# sensor.net
KiCad netlist of a schematic drawn in EAGLE
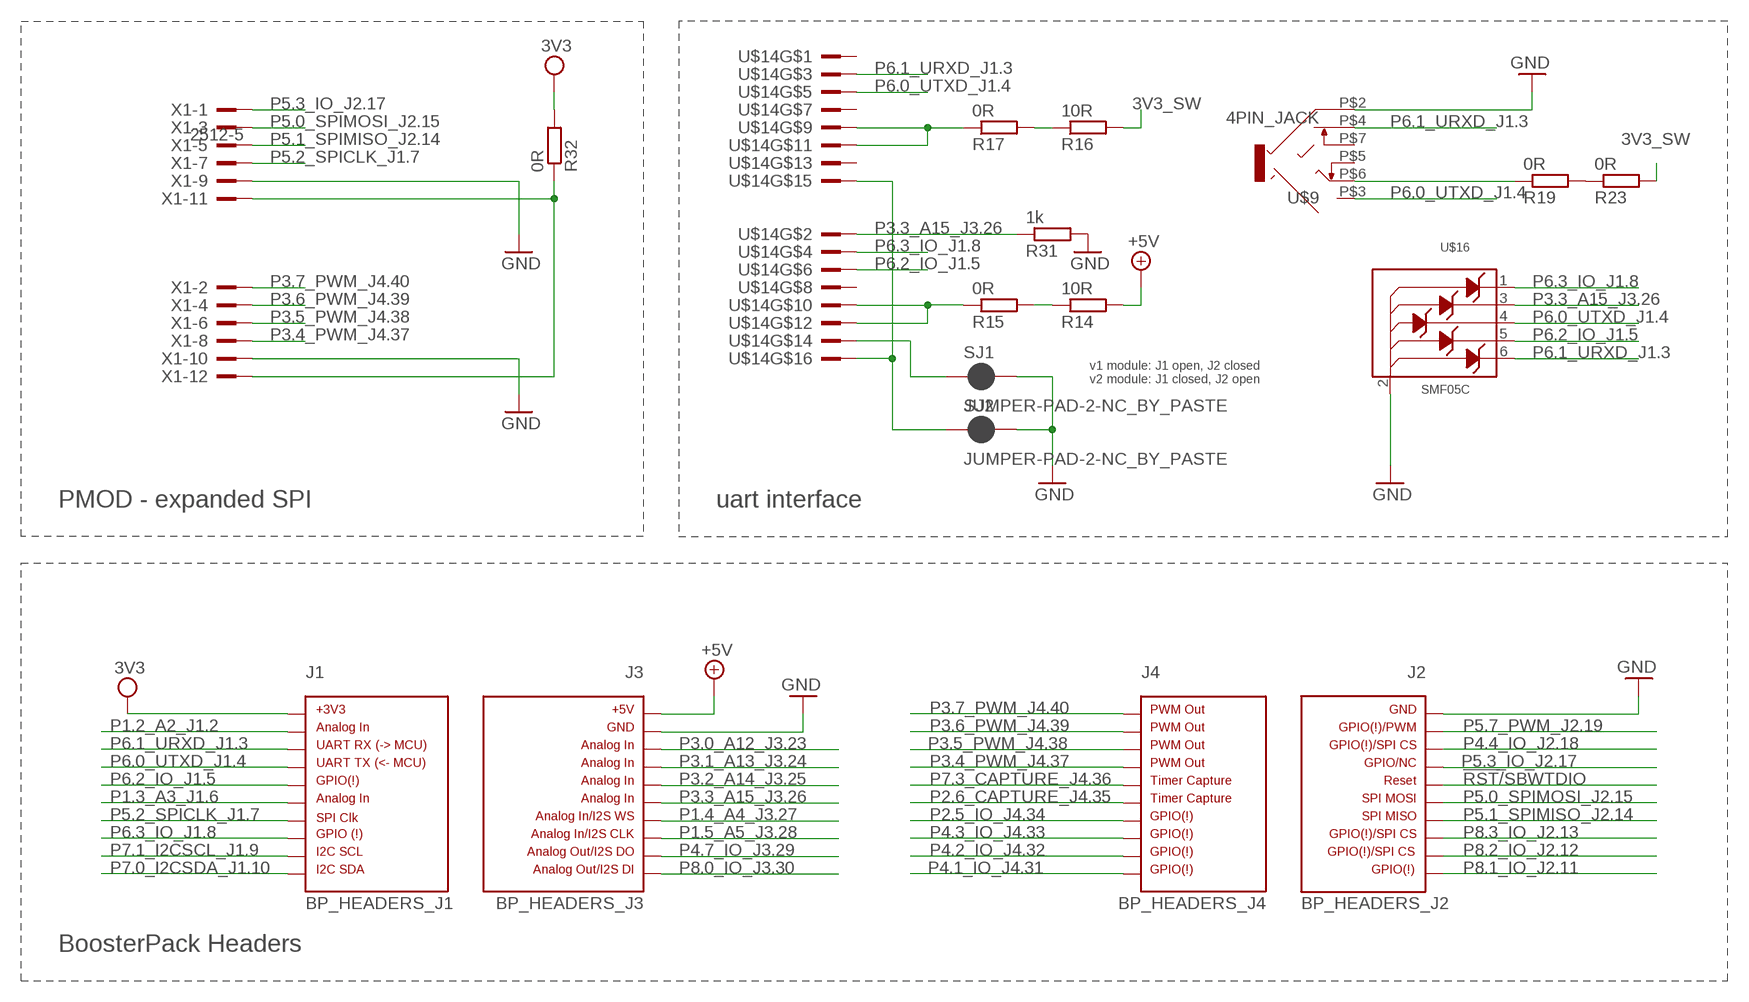
[diagram p0: schematic, sheet 1]
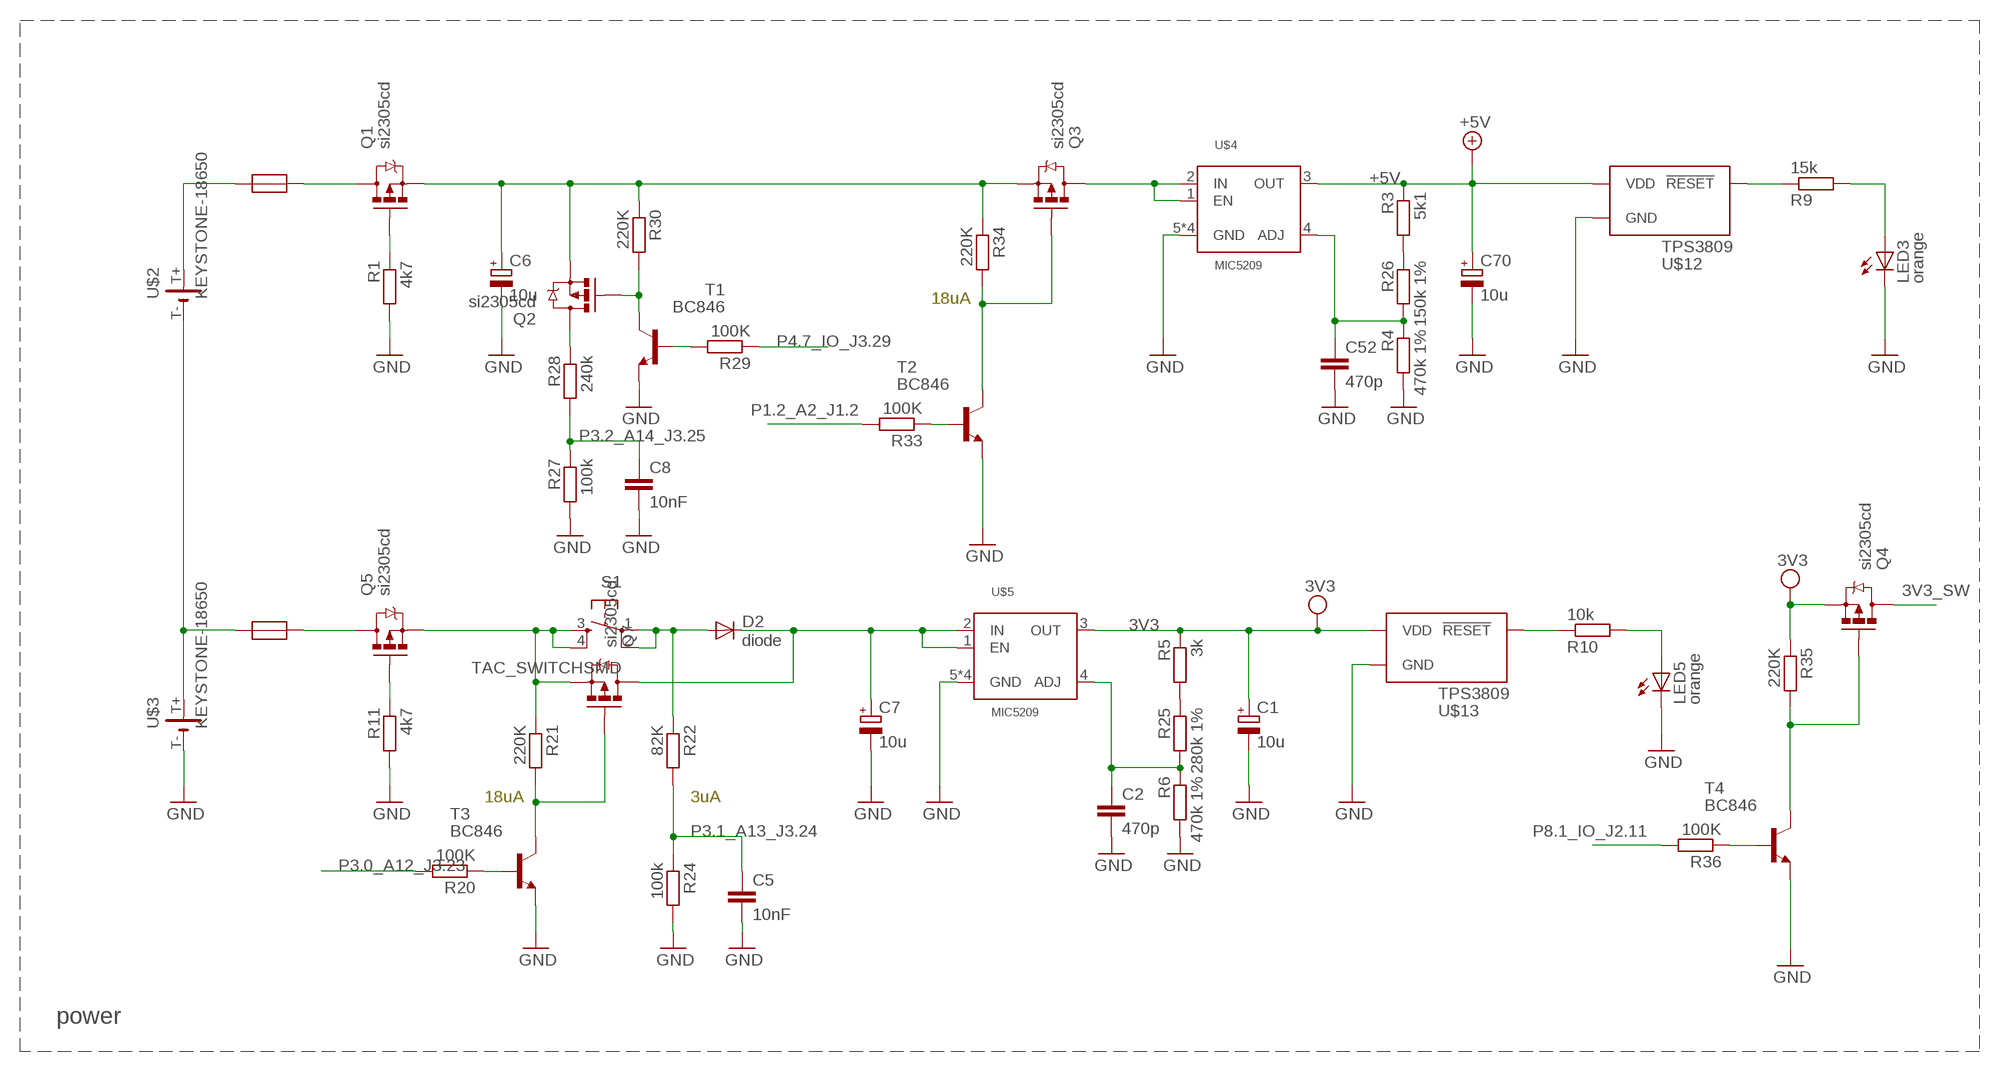
[diagram p1: schematic, sheet 2]
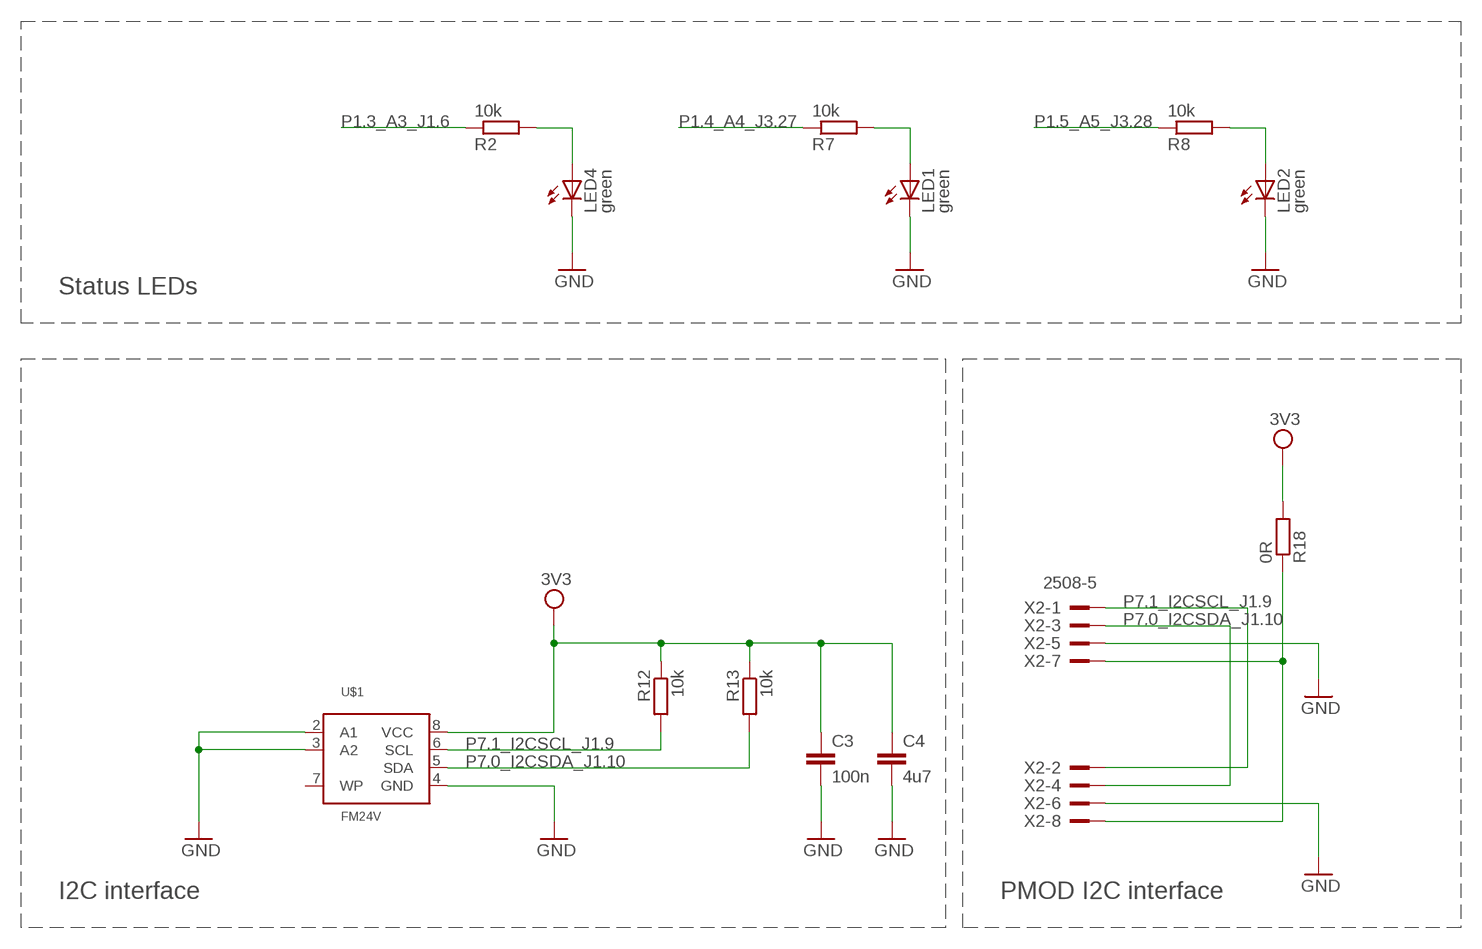
[diagram p2: schematic, sheet 3]

(export (version "E")
  (design (tool "Eeschema 10.0.6"))
  (components
    (comp (ref "J1")
      (value "BP_HEADERS_J1")
      (footprint "eagle-import:J1")
      (libsource (lib "eagle-import") (part "BP_HEADERS_J1"))
    )
    (comp (ref "J2")
      (value "BP_HEADERS_J2")
      (footprint "eagle-import:J2")
      (libsource (lib "eagle-import") (part "BP_HEADERS_J2"))
    )
    (comp (ref "J3")
      (value "BP_HEADERS_J3")
      (footprint "eagle-import:J3")
      (libsource (lib "eagle-import") (part "BP_HEADERS_J3"))
    )
    (comp (ref "J4")
      (value "BP_HEADERS_J4")
      (footprint "eagle-import:J4")
      (libsource (lib "eagle-import") (part "BP_HEADERS_J4"))
    )
    (comp (ref "R14")
      (value "10R")
      (footprint "eagle-import:R0805W")
      (libsource (lib "eagle-import") (part "R-EU_R0805W"))
    )
    (comp (ref "R15")
      (value "0R")
      (footprint "eagle-import:0204V")
      (libsource (lib "eagle-import") (part "R-EU_0204/2V"))
    )
    (comp (ref "R16")
      (value "10R")
      (footprint "eagle-import:R0805W")
      (libsource (lib "eagle-import") (part "R-EU_R0805W"))
    )
    (comp (ref "R17")
      (value "0R")
      (footprint "eagle-import:0204V")
      (libsource (lib "eagle-import") (part "R-EU_0204/2V"))
    )
    (comp (ref "R19")
      (value "0R")
      (footprint "eagle-import:0204V")
      (libsource (lib "eagle-import") (part "R-EU_0204/2V"))
    )
    (comp (ref "R23")
      (value "0R")
      (footprint "eagle-import:R0805W")
      (libsource (lib "eagle-import") (part "R-EU_R0805W"))
    )
    (comp (ref "R31")
      (value "1k")
      (footprint "eagle-import:R0805W")
      (libsource (lib "eagle-import") (part "R-EU_R0805W"))
    )
    (comp (ref "R32")
      (value "0R")
      (footprint "eagle-import:0204V")
      (libsource (lib "eagle-import") (part "R-EU_0204/2V"))
    )
    (comp (ref "SJ1")
      (value "JUMPER-PAD-2-NC_BY_PASTE")
      (footprint "eagle-import:PAD-JUMPER-2-NC_BY_PASTE_YES_SILK")
      (libsource (lib "eagle-import") (part "JUMPER-PAD-2-NC_BY_PASTE"))
    )
    (comp (ref "SJ2")
      (value "JUMPER-PAD-2-NC_BY_PASTE")
      (footprint "eagle-import:PAD-JUMPER-2-NC_BY_PASTE_YES_SILK")
      (libsource (lib "eagle-import") (part "JUMPER-PAD-2-NC_BY_PASTE"))
    )
    (comp (ref "U$9")
      (value "4PIN_JACK")
      (footprint "eagle-import:4PIN_JACK")
      (libsource (lib "eagle-import") (part "4PIN_JACK"))
    )
    (comp (ref "U$14")
      (value "2516-")
      (footprint "eagle-import:PAK100_2500-5-16")
      (libsource (lib "eagle-import") (part "2516-"))
    )
    (comp (ref "U$16")
      (value "SMF05C")
      (footprint "eagle-import:SC-88")
      (libsource (lib "eagle-import") (part "SMF05C"))
    )
    (comp (ref "X1")
      (value "2512-5")
      (footprint "eagle-import:PAK100_2500-5-12")
      (fields (field (name "MPN") "N2514-5002RB"))
      (libsource (lib "eagle-import") (part "2512-5"))
    )
    (comp (ref "C1")
      (value "10u")
      (footprint "eagle-import:153CLV-0405")
      (libsource (lib "eagle-import") (part "CPOL-EU153CLV-0405"))
    )
    (comp (ref "C2")
      (value "470p")
      (footprint "eagle-import:C0805")
      (libsource (lib "eagle-import") (part "C-EUC0805"))
    )
    (comp (ref "C5")
      (value "10nF")
      (footprint "eagle-import:C0805")
      (libsource (lib "eagle-import") (part "C-EUC0805"))
    )
    (comp (ref "C6")
      (value "10u")
      (footprint "eagle-import:153CLV-0405")
      (libsource (lib "eagle-import") (part "CPOL-EU153CLV-0405"))
    )
    (comp (ref "C7")
      (value "10u")
      (footprint "eagle-import:153CLV-0405")
      (libsource (lib "eagle-import") (part "CPOL-EU153CLV-0405"))
    )
    (comp (ref "C8")
      (value "10nF")
      (footprint "eagle-import:C0805")
      (libsource (lib "eagle-import") (part "C-EUC0805"))
    )
    (comp (ref "C52")
      (value "470p")
      (footprint "eagle-import:C0805")
      (libsource (lib "eagle-import") (part "C-EUC0805"))
    )
    (comp (ref "C70")
      (value "10u")
      (footprint "eagle-import:153CLV-0405")
      (libsource (lib "eagle-import") (part "CPOL-EU153CLV-0405"))
    )
    (comp (ref "D2")
      (value "diode")
      (footprint "eagle-import:SMA-DIODE")
      (libsource (lib "eagle-import") (part "DIODESMA"))
    )
    (comp (ref "LED3")
      (value "orange")
      (footprint "eagle-import:CHIPLED_0805")
      (libsource (lib "eagle-import") (part "LEDCHIPLED_0805"))
    )
    (comp (ref "LED5")
      (value "orange")
      (footprint "eagle-import:CHIPLED_0805")
      (libsource (lib "eagle-import") (part "LEDCHIPLED_0805"))
    )
    (comp (ref "Q1")
      (value "si2305cd")
      (footprint "eagle-import:SOT23-3_POWER")
      (libsource (lib "eagle-import") (part "MOSFET-PCHANNELSMD_POWER"))
    )
    (comp (ref "Q2")
      (value "si2305cd")
      (footprint "eagle-import:SOT23-3_POWER")
      (libsource (lib "eagle-import") (part "MOSFET-PCHANNELSMD_POWER"))
    )
    (comp (ref "Q3")
      (value "si2305cd")
      (footprint "eagle-import:SOT23-3_POWER")
      (libsource (lib "eagle-import") (part "MOSFET-PCHANNELSMD_POWER"))
    )
    (comp (ref "Q4")
      (value "si2305cd")
      (footprint "eagle-import:SOT23-3_POWER")
      (libsource (lib "eagle-import") (part "MOSFET-PCHANNELSMD_POWER"))
    )
    (comp (ref "Q5")
      (value "si2305cd")
      (footprint "eagle-import:SOT23-3_POWER")
      (libsource (lib "eagle-import") (part "MOSFET-PCHANNELSMD_POWER"))
    )
    (comp (ref "Q7")
      (value "si2305cd")
      (footprint "eagle-import:SOT23-3_POWER")
      (libsource (lib "eagle-import") (part "MOSFET-PCHANNELSMD_POWER"))
    )
    (comp (ref "R1")
      (value "4k7")
      (footprint "eagle-import:R0805W")
      (libsource (lib "eagle-import") (part "R-EU_R0805W"))
    )
    (comp (ref "R3")
      (value "5k1")
      (footprint "eagle-import:R0805W")
      (libsource (lib "eagle-import") (part "R-EU_R0805W"))
    )
    (comp (ref "R4")
      (value "470k 1%")
      (footprint "eagle-import:R0805W")
      (libsource (lib "eagle-import") (part "R-EU_R0805W"))
    )
    (comp (ref "R5")
      (value "3k")
      (footprint "eagle-import:R0805W")
      (libsource (lib "eagle-import") (part "R-EU_R0805W"))
    )
    (comp (ref "R6")
      (value "470k 1%")
      (footprint "eagle-import:R0805W")
      (libsource (lib "eagle-import") (part "R-EU_R0805W"))
    )
    (comp (ref "R9")
      (value "15k")
      (footprint "eagle-import:R0805W")
      (libsource (lib "eagle-import") (part "R-EU_R0805W"))
    )
    (comp (ref "R10")
      (value "10k")
      (footprint "eagle-import:R0805W")
      (libsource (lib "eagle-import") (part "R-EU_R0805W"))
    )
    (comp (ref "R11")
      (value "4k7")
      (footprint "eagle-import:R0805W")
      (libsource (lib "eagle-import") (part "R-EU_R0805W"))
    )
    (comp (ref "R20")
      (value "100K")
      (footprint "eagle-import:R0805W")
      (libsource (lib "eagle-import") (part "R-EU_R0805W"))
    )
    (comp (ref "R21")
      (value "220K")
      (footprint "eagle-import:R0805W")
      (libsource (lib "eagle-import") (part "R-EU_R0805W"))
    )
    (comp (ref "R22")
      (value "82K")
      (footprint "eagle-import:R0805W")
      (libsource (lib "eagle-import") (part "R-EU_R0805W"))
    )
    (comp (ref "R24")
      (value "100k")
      (footprint "eagle-import:R0805W")
      (libsource (lib "eagle-import") (part "R-EU_R0805W"))
    )
    (comp (ref "R25")
      (value "280k 1%")
      (footprint "eagle-import:R0805W")
      (libsource (lib "eagle-import") (part "R-EU_R0805W"))
    )
    (comp (ref "R26")
      (value "150k 1%")
      (footprint "eagle-import:R0805W")
      (libsource (lib "eagle-import") (part "R-EU_R0805W"))
    )
    (comp (ref "R27")
      (value "100k")
      (footprint "eagle-import:R0805W")
      (libsource (lib "eagle-import") (part "R-EU_R0805W"))
    )
    (comp (ref "R28")
      (value "240k")
      (footprint "eagle-import:R0805W")
      (libsource (lib "eagle-import") (part "R-EU_R0805W"))
    )
    (comp (ref "R29")
      (value "100K")
      (footprint "eagle-import:R0805W")
      (libsource (lib "eagle-import") (part "R-EU_R0805W"))
    )
    (comp (ref "R30")
      (value "220K")
      (footprint "eagle-import:R0805W")
      (libsource (lib "eagle-import") (part "R-EU_R0805W"))
    )
    (comp (ref "R33")
      (value "100K")
      (footprint "eagle-import:R0805W")
      (libsource (lib "eagle-import") (part "R-EU_R0805W"))
    )
    (comp (ref "R34")
      (value "220K")
      (footprint "eagle-import:R0805W")
      (libsource (lib "eagle-import") (part "R-EU_R0805W"))
    )
    (comp (ref "R35")
      (value "220K")
      (footprint "eagle-import:R0805W")
      (libsource (lib "eagle-import") (part "R-EU_R0805W"))
    )
    (comp (ref "R36")
      (value "100K")
      (footprint "eagle-import:R0805W")
      (libsource (lib "eagle-import") (part "R-EU_R0805W"))
    )
    (comp (ref "S1")
      (value "TAC_SWITCHSMD")
      (footprint "eagle-import:TACTILE-SWITCH-SMD")
      (libsource (lib "eagle-import") (part "TAC_SWITCHSMD"))
    )
    (comp (ref "T1")
      (value "BC846")
      (footprint "eagle-import:SOT23")
      (libsource (lib "eagle-import") (part "BC846"))
    )
    (comp (ref "T2")
      (value "BC846")
      (footprint "eagle-import:SOT23")
      (libsource (lib "eagle-import") (part "BC846"))
    )
    (comp (ref "T3")
      (value "BC846")
      (footprint "eagle-import:SOT23")
      (libsource (lib "eagle-import") (part "BC846"))
    )
    (comp (ref "T4")
      (value "BC846")
      (footprint "eagle-import:SOT23")
      (libsource (lib "eagle-import") (part "BC846"))
    )
    (comp (ref "U$2")
      (value "KEYSTONE-18650")
      (footprint "eagle-import:KEYSTONE_COMBO_18650")
      (libsource (lib "eagle-import") (part "KEYSTONE-18650"))
    )
    (comp (ref "U$3")
      (value "KEYSTONE-18650")
      (footprint "eagle-import:KEYSTONE_COMBO_18650")
      (libsource (lib "eagle-import") (part "KEYSTONE-18650"))
    )
    (comp (ref "U$4")
      (value "MIC5209")
      (footprint "eagle-import:SO-08")
      (libsource (lib "eagle-import") (part "MIC5209"))
    )
    (comp (ref "U$5")
      (value "MIC5209")
      (footprint "eagle-import:SO-08")
      (libsource (lib "eagle-import") (part "MIC5209"))
    )
    (comp (ref "U$7")
      (value "Fuse 1A")
      (footprint "eagle-import:0805W")
      (libsource (lib "eagle-import") (part "RESETTABLE_0805"))
    )
    (comp (ref "U$8")
      (value "Fuse 1A")
      (footprint "eagle-import:0805W")
      (libsource (lib "eagle-import") (part "RESETTABLE_0805"))
    )
    (comp (ref "U$12")
      (value "TPS3809")
      (footprint "eagle-import:R_PDSO_G3")
      (libsource (lib "eagle-import") (part "TPS3809"))
    )
    (comp (ref "U$13")
      (value "TPS3809")
      (footprint "eagle-import:R_PDSO_G3")
      (libsource (lib "eagle-import") (part "TPS3809"))
    )
    (comp (ref "C3")
      (value "100n")
      (footprint "eagle-import:C0805")
      (libsource (lib "eagle-import") (part "C-EUC0805"))
    )
    (comp (ref "C4")
      (value "4u7")
      (footprint "eagle-import:C0805")
      (libsource (lib "eagle-import") (part "C-EUC0805"))
    )
    (comp (ref "LED1")
      (value "green")
      (footprint "eagle-import:CHIPLED_0805")
      (libsource (lib "eagle-import") (part "LEDCHIPLED_0805"))
    )
    (comp (ref "LED2")
      (value "green")
      (footprint "eagle-import:CHIPLED_0805")
      (libsource (lib "eagle-import") (part "LEDCHIPLED_0805"))
    )
    (comp (ref "LED4")
      (value "green")
      (footprint "eagle-import:CHIPLED_0805")
      (libsource (lib "eagle-import") (part "LEDCHIPLED_0805"))
    )
    (comp (ref "R2")
      (value "10k")
      (footprint "eagle-import:R0805W")
      (libsource (lib "eagle-import") (part "R-EU_R0805W"))
    )
    (comp (ref "R7")
      (value "10k")
      (footprint "eagle-import:R0805W")
      (libsource (lib "eagle-import") (part "R-EU_R0805W"))
    )
    (comp (ref "R8")
      (value "10k")
      (footprint "eagle-import:R0805W")
      (libsource (lib "eagle-import") (part "R-EU_R0805W"))
    )
    (comp (ref "R12")
      (value "10k")
      (footprint "eagle-import:R0805W")
      (libsource (lib "eagle-import") (part "R-EU_R0805W"))
    )
    (comp (ref "R13")
      (value "10k")
      (footprint "eagle-import:R0805W")
      (libsource (lib "eagle-import") (part "R-EU_R0805W"))
    )
    (comp (ref "R18")
      (value "0R")
      (footprint "eagle-import:0204V")
      (libsource (lib "eagle-import") (part "R-EU_0204/2V"))
    )
    (comp (ref "U$1")
      (value "FM24V")
      (footprint "eagle-import:SO-08")
      (libsource (lib "eagle-import") (part "FM24V"))
    )
    (comp (ref "X2")
      (value "2508-5")
      (footprint "eagle-import:PAK100_2500-5-08")
      (libsource (lib "eagle-import") (part "2508-5"))
    )
  )
  (nets
    (net (code "1") (name "+5V") (class "Default")
      (node (ref "C70") (pin "+") (pinfunction "+_+") (pintype "passive"))
      (node (ref "J3") (pin "21") (pinfunction "21_21") (pintype "bidirectional"))
      (node (ref "R14") (pin "2") (pinfunction "2_2") (pintype "passive"))
      (node (ref "R3") (pin "1") (pinfunction "1_1") (pintype "passive"))
      (node (ref "U$12") (pin "P$3") (pinfunction "VDD_P$3") (pintype "bidirectional"))
      (node (ref "U$4") (pin "3") (pinfunction "OUT_3") (pintype "bidirectional"))
    )
    (net (code "2") (name "3V3") (class "Default")
      (node (ref "C1") (pin "+") (pinfunction "+_+") (pintype "passive"))
      (node (ref "C3") (pin "1") (pinfunction "1_1") (pintype "passive"))
      (node (ref "C4") (pin "1") (pinfunction "1_1") (pintype "passive"))
      (node (ref "J1") (pin "1") (pinfunction "1_1") (pintype "bidirectional"))
      (node (ref "Q4") (pin "2") (pinfunction "S_2") (pintype "passive"))
      (node (ref "R12") (pin "1") (pinfunction "1_1") (pintype "passive"))
      (node (ref "R13") (pin "1") (pinfunction "1_1") (pintype "passive"))
      (node (ref "R18") (pin "2") (pinfunction "2_2") (pintype "passive"))
      (node (ref "R32") (pin "2") (pinfunction "2_2") (pintype "passive"))
      (node (ref "R35") (pin "1") (pinfunction "1_1") (pintype "passive"))
      (node (ref "R5") (pin "1") (pinfunction "1_1") (pintype "passive"))
      (node (ref "U$1") (pin "8") (pinfunction "VCC_8") (pintype "bidirectional"))
      (node (ref "U$13") (pin "P$3") (pinfunction "VDD_P$3") (pintype "bidirectional"))
      (node (ref "U$5") (pin "3") (pinfunction "OUT_3") (pintype "bidirectional"))
    )
    (net (code "3") (name "3V3_SW") (class "Default")
      (node (ref "Q4") (pin "3") (pinfunction "D_3") (pintype "passive"))
      (node (ref "R16") (pin "2") (pinfunction "2_2") (pintype "passive"))
      (node (ref "R23") (pin "2") (pinfunction "2_2") (pintype "passive"))
    )
    (net (code "4") (name "GND") (class "Default")
      (node (ref "C1") (pin "-") (pinfunction "-_-") (pintype "passive"))
      (node (ref "C2") (pin "2") (pinfunction "2_2") (pintype "passive"))
      (node (ref "C3") (pin "2") (pinfunction "2_2") (pintype "passive"))
      (node (ref "C4") (pin "2") (pinfunction "2_2") (pintype "passive"))
      (node (ref "C5") (pin "2") (pinfunction "2_2") (pintype "passive"))
      (node (ref "C52") (pin "2") (pinfunction "2_2") (pintype "passive"))
      (node (ref "C6") (pin "-") (pinfunction "-_-") (pintype "passive"))
      (node (ref "C7") (pin "-") (pinfunction "-_-") (pintype "passive"))
      (node (ref "C70") (pin "-") (pinfunction "-_-") (pintype "passive"))
      (node (ref "C8") (pin "2") (pinfunction "2_2") (pintype "passive"))
      (node (ref "J2") (pin "20") (pinfunction "20_20") (pintype "bidirectional"))
      (node (ref "J3") (pin "22") (pinfunction "22_22") (pintype "bidirectional"))
      (node (ref "LED1") (pin "C") (pinfunction "C_C") (pintype "passive"))
      (node (ref "LED2") (pin "C") (pinfunction "C_C") (pintype "passive"))
      (node (ref "LED3") (pin "C") (pinfunction "C_C") (pintype "passive"))
      (node (ref "LED4") (pin "C") (pinfunction "C_C") (pintype "passive"))
      (node (ref "LED5") (pin "C") (pinfunction "C_C") (pintype "passive"))
      (node (ref "R1") (pin "2") (pinfunction "2_2") (pintype "passive"))
      (node (ref "R11") (pin "2") (pinfunction "2_2") (pintype "passive"))
      (node (ref "R24") (pin "2") (pinfunction "2_2") (pintype "passive"))
      (node (ref "R27") (pin "2") (pinfunction "2_2") (pintype "passive"))
      (node (ref "R31") (pin "2") (pinfunction "2_2") (pintype "passive"))
      (node (ref "R4") (pin "2") (pinfunction "2_2") (pintype "passive"))
      (node (ref "R6") (pin "2") (pinfunction "2_2") (pintype "passive"))
      (node (ref "SJ1") (pin "2") (pinfunction "2_2") (pintype "passive"))
      (node (ref "SJ2") (pin "2") (pinfunction "2_2") (pintype "passive"))
      (node (ref "T1") (pin "2") (pinfunction "E_2") (pintype "passive"))
      (node (ref "T2") (pin "2") (pinfunction "E_2") (pintype "passive"))
      (node (ref "T3") (pin "2") (pinfunction "E_2") (pintype "passive"))
      (node (ref "T4") (pin "2") (pinfunction "E_2") (pintype "passive"))
      (node (ref "U$1") (pin "2") (pinfunction "A1_2") (pintype "bidirectional"))
      (node (ref "U$1") (pin "3") (pinfunction "A2_3") (pintype "bidirectional"))
      (node (ref "U$1") (pin "4") (pinfunction "GND_4") (pintype "bidirectional"))
      (node (ref "U$12") (pin "P$1") (pinfunction "GND_P$1") (pintype "bidirectional"))
      (node (ref "U$13") (pin "P$1") (pinfunction "GND_P$1") (pintype "bidirectional"))
      (node (ref "U$16") (pin "2") (pinfunction "ANODE_2") (pintype "passive"))
      (node (ref "U$3") (pin "T-") (pinfunction "-_T-") (pintype "passive"))
      (node (ref "U$4") (pin "5") (pinfunction "GND_5") (pintype "bidirectional"))
      (node (ref "U$4") (pin "6") (pinfunction "GND_6") (pintype "bidirectional"))
      (node (ref "U$4") (pin "7") (pinfunction "GND_7") (pintype "bidirectional"))
      (node (ref "U$4") (pin "8") (pinfunction "GND_8") (pintype "bidirectional"))
      (node (ref "U$5") (pin "5") (pinfunction "GND_5") (pintype "bidirectional"))
      (node (ref "U$5") (pin "6") (pinfunction "GND_6") (pintype "bidirectional"))
      (node (ref "U$5") (pin "7") (pinfunction "GND_7") (pintype "bidirectional"))
      (node (ref "U$5") (pin "8") (pinfunction "GND_8") (pintype "bidirectional"))
      (node (ref "U$9") (pin "P$2") (pinfunction "2_P$2") (pintype "passive"))
      (node (ref "X1") (pin "10") (pinfunction "KL_10") (pintype "passive"))
      (node (ref "X1") (pin "9") (pinfunction "KL_9") (pintype "passive"))
      (node (ref "X2") (pin "5") (pinfunction "KL_5") (pintype "passive"))
      (node (ref "X2") (pin "6") (pinfunction "KL_6") (pintype "passive"))
    )
    (net (code "5") (name "Net-(D2-PadA)") (class "Default")
      (node (ref "D2") (pin "A") (pinfunction "A_A") (pintype "passive"))
      (node (ref "R22") (pin "1") (pinfunction "1_1") (pintype "passive"))
      (node (ref "S1") (pin "1") (pinfunction "1_1") (pintype "passive"))
      (node (ref "S1") (pin "2") (pinfunction "2_2") (pintype "passive"))
    )
    (net (code "6") (name "Net-(LED1-PadA)") (class "Default")
      (node (ref "LED1") (pin "A") (pinfunction "A_A") (pintype "passive"))
      (node (ref "R7") (pin "2") (pinfunction "2_2") (pintype "passive"))
    )
    (net (code "7") (name "Net-(LED2-PadA)") (class "Default")
      (node (ref "LED2") (pin "A") (pinfunction "A_A") (pintype "passive"))
      (node (ref "R8") (pin "2") (pinfunction "2_2") (pintype "passive"))
    )
    (net (code "8") (name "Net-(LED3-PadA)") (class "Default")
      (node (ref "LED3") (pin "A") (pinfunction "A_A") (pintype "passive"))
      (node (ref "R9") (pin "2") (pinfunction "2_2") (pintype "passive"))
    )
    (net (code "9") (name "Net-(LED4-PadA)") (class "Default")
      (node (ref "LED4") (pin "A") (pinfunction "A_A") (pintype "passive"))
      (node (ref "R2") (pin "2") (pinfunction "2_2") (pintype "passive"))
    )
    (net (code "10") (name "Net-(LED5-PadA)") (class "Default")
      (node (ref "LED5") (pin "A") (pinfunction "A_A") (pintype "passive"))
      (node (ref "R10") (pin "2") (pinfunction "2_2") (pintype "passive"))
    )
    (net (code "11") (name "Net-(Q1-D)") (class "Default")
      (node (ref "Q1") (pin "3") (pinfunction "D_3") (pintype "passive"))
      (node (ref "U$7") (pin "2") (pinfunction "P$2_2") (pintype "bidirectional"))
    )
    (net (code "12") (name "Net-(Q1-G)") (class "Default")
      (node (ref "Q1") (pin "1") (pinfunction "G_1") (pintype "passive"))
      (node (ref "R1") (pin "1") (pinfunction "1_1") (pintype "passive"))
    )
    (net (code "13") (name "Net-(Q1-S)") (class "Default")
      (node (ref "C6") (pin "+") (pinfunction "+_+") (pintype "passive"))
      (node (ref "Q1") (pin "2") (pinfunction "S_2") (pintype "passive"))
      (node (ref "Q2") (pin "2") (pinfunction "S_2") (pintype "passive"))
      (node (ref "Q3") (pin "2") (pinfunction "S_2") (pintype "passive"))
      (node (ref "R30") (pin "1") (pinfunction "1_1") (pintype "passive"))
      (node (ref "R34") (pin "1") (pinfunction "1_1") (pintype "passive"))
    )
    (net (code "14") (name "Net-(Q2-D)") (class "Default")
      (node (ref "Q2") (pin "3") (pinfunction "D_3") (pintype "passive"))
      (node (ref "R28") (pin "1") (pinfunction "1_1") (pintype "passive"))
    )
    (net (code "15") (name "Net-(Q2-G)") (class "Default")
      (node (ref "Q2") (pin "1") (pinfunction "G_1") (pintype "passive"))
      (node (ref "R30") (pin "2") (pinfunction "2_2") (pintype "passive"))
      (node (ref "T1") (pin "3") (pinfunction "C_3") (pintype "passive"))
    )
    (net (code "16") (name "Net-(Q3-D)") (class "Default")
      (node (ref "Q3") (pin "3") (pinfunction "D_3") (pintype "passive"))
      (node (ref "U$4") (pin "1") (pinfunction "EN_1") (pintype "bidirectional"))
      (node (ref "U$4") (pin "2") (pinfunction "IN_2") (pintype "bidirectional"))
    )
    (net (code "17") (name "Net-(Q3-G)") (class "Default")
      (node (ref "Q3") (pin "1") (pinfunction "G_1") (pintype "passive"))
      (node (ref "R34") (pin "2") (pinfunction "2_2") (pintype "passive"))
      (node (ref "T2") (pin "3") (pinfunction "C_3") (pintype "passive"))
    )
    (net (code "18") (name "Net-(Q4-G)") (class "Default")
      (node (ref "Q4") (pin "1") (pinfunction "G_1") (pintype "passive"))
      (node (ref "R35") (pin "2") (pinfunction "2_2") (pintype "passive"))
      (node (ref "T4") (pin "3") (pinfunction "C_3") (pintype "passive"))
    )
    (net (code "19") (name "Net-(Q5-D)") (class "Default")
      (node (ref "Q5") (pin "3") (pinfunction "D_3") (pintype "passive"))
      (node (ref "U$8") (pin "2") (pinfunction "P$2_2") (pintype "bidirectional"))
    )
    (net (code "20") (name "Net-(Q5-G)") (class "Default")
      (node (ref "Q5") (pin "1") (pinfunction "G_1") (pintype "passive"))
      (node (ref "R11") (pin "1") (pinfunction "1_1") (pintype "passive"))
    )
    (net (code "21") (name "Net-(Q5-S)") (class "Default")
      (node (ref "Q5") (pin "2") (pinfunction "S_2") (pintype "passive"))
      (node (ref "Q7") (pin "2") (pinfunction "S_2") (pintype "passive"))
      (node (ref "R21") (pin "1") (pinfunction "1_1") (pintype "passive"))
      (node (ref "S1") (pin "3") (pinfunction "3_3") (pintype "passive"))
      (node (ref "S1") (pin "4") (pinfunction "4_4") (pintype "passive"))
    )
    (net (code "22") (name "Net-(Q7-D)") (class "Default")
      (node (ref "C7") (pin "+") (pinfunction "+_+") (pintype "passive"))
      (node (ref "D2") (pin "C") (pinfunction "C_C") (pintype "passive"))
      (node (ref "Q7") (pin "3") (pinfunction "D_3") (pintype "passive"))
      (node (ref "U$5") (pin "1") (pinfunction "EN_1") (pintype "bidirectional"))
      (node (ref "U$5") (pin "2") (pinfunction "IN_2") (pintype "bidirectional"))
    )
    (net (code "23") (name "Net-(Q7-G)") (class "Default")
      (node (ref "Q7") (pin "1") (pinfunction "G_1") (pintype "passive"))
      (node (ref "R21") (pin "2") (pinfunction "2_2") (pintype "passive"))
      (node (ref "T3") (pin "3") (pinfunction "C_3") (pintype "passive"))
    )
    (net (code "24") (name "Net-(R14-Pad1)") (class "Default")
      (node (ref "R14") (pin "1") (pinfunction "1_1") (pintype "passive"))
      (node (ref "R15") (pin "2") (pinfunction "2_2") (pintype "passive"))
    )
    (net (code "25") (name "Net-(R16-Pad1)") (class "Default")
      (node (ref "R16") (pin "1") (pinfunction "1_1") (pintype "passive"))
      (node (ref "R17") (pin "2") (pinfunction "2_2") (pintype "passive"))
    )
    (net (code "26") (name "Net-(R19-Pad2)") (class "Default")
      (node (ref "R19") (pin "2") (pinfunction "2_2") (pintype "passive"))
      (node (ref "R23") (pin "1") (pinfunction "1_1") (pintype "passive"))
    )
    (net (code "27") (name "Net-(R25-Pad1)") (class "Default")
      (node (ref "R25") (pin "1") (pinfunction "1_1") (pintype "passive"))
      (node (ref "R5") (pin "2") (pinfunction "2_2") (pintype "passive"))
    )
    (net (code "28") (name "Net-(R26-Pad1)") (class "Default")
      (node (ref "R26") (pin "1") (pinfunction "1_1") (pintype "passive"))
      (node (ref "R3") (pin "2") (pinfunction "2_2") (pintype "passive"))
    )
    (net (code "29") (name "Net-(T1-B)") (class "Default")
      (node (ref "R29") (pin "2") (pinfunction "2_2") (pintype "passive"))
      (node (ref "T1") (pin "1") (pinfunction "B_1") (pintype "passive"))
    )
    (net (code "30") (name "Net-(T2-B)") (class "Default")
      (node (ref "R33") (pin "1") (pinfunction "1_1") (pintype "passive"))
      (node (ref "T2") (pin "1") (pinfunction "B_1") (pintype "passive"))
    )
    (net (code "31") (name "Net-(T3-B)") (class "Default")
      (node (ref "R20") (pin "1") (pinfunction "1_1") (pintype "passive"))
      (node (ref "T3") (pin "1") (pinfunction "B_1") (pintype "passive"))
    )
    (net (code "32") (name "Net-(T4-B)") (class "Default")
      (node (ref "R36") (pin "1") (pinfunction "1_1") (pintype "passive"))
      (node (ref "T4") (pin "1") (pinfunction "B_1") (pintype "passive"))
    )
    (net (code "33") (name "Net-(U$2-+)") (class "Default")
      (node (ref "U$2") (pin "T+") (pinfunction "+_T+") (pintype "passive"))
      (node (ref "U$7") (pin "1") (pinfunction "P$1_1") (pintype "bidirectional"))
    )
    (net (code "34") (name "Net-(U$2--)") (class "Default")
      (node (ref "U$2") (pin "T-") (pinfunction "-_T-") (pintype "passive"))
      (node (ref "U$3") (pin "T+") (pinfunction "+_T+") (pintype "passive"))
      (node (ref "U$8") (pin "1") (pinfunction "P$1_1") (pintype "bidirectional"))
    )
    (net (code "35") (name "Net-(U$4-ADJ)") (class "Default")
      (node (ref "C52") (pin "1") (pinfunction "1_1") (pintype "passive"))
      (node (ref "R26") (pin "2") (pinfunction "2_2") (pintype "passive"))
      (node (ref "R4") (pin "1") (pinfunction "1_1") (pintype "passive"))
      (node (ref "U$4") (pin "4") (pinfunction "ADJ_4") (pintype "bidirectional"))
    )
    (net (code "36") (name "Net-(U$5-ADJ)") (class "Default")
      (node (ref "C2") (pin "1") (pinfunction "1_1") (pintype "passive"))
      (node (ref "R25") (pin "2") (pinfunction "2_2") (pintype "passive"))
      (node (ref "R6") (pin "1") (pinfunction "1_1") (pintype "passive"))
      (node (ref "U$5") (pin "4") (pinfunction "ADJ_4") (pintype "bidirectional"))
    )
    (net (code "37") (name "Net-(U$9-6)") (class "Default")
      (node (ref "R19") (pin "1") (pinfunction "1_1") (pintype "passive"))
      (node (ref "U$9") (pin "P$6") (pinfunction "6_P$6") (pintype "passive"))
    )
    (net (code "38") (name "Net-(U$12-~{RESET})") (class "Default")
      (node (ref "R9") (pin "1") (pinfunction "1_1") (pintype "passive"))
      (node (ref "U$12") (pin "P$2") (pinfunction "~{RESET}_P$2") (pintype "bidirectional"))
    )
    (net (code "39") (name "Net-(U$13-~{RESET})") (class "Default")
      (node (ref "R10") (pin "1") (pinfunction "1_1") (pintype "passive"))
      (node (ref "U$13") (pin "P$2") (pinfunction "~{RESET}_P$2") (pintype "bidirectional"))
    )
    (net (code "40") (name "Net-(U$14B-KL)") (class "Default")
      (node (ref "R15") (pin "1") (pinfunction "1_1") (pintype "passive"))
      (node (ref "U$14") (pin "10") (pinfunction "KL_10") (pintype "passive"))
      (node (ref "U$14") (pin "12") (pinfunction "KL_12") (pintype "passive"))
    )
    (net (code "41") (name "Net-(U$14C-KL)") (class "Default")
      (node (ref "R17") (pin "1") (pinfunction "1_1") (pintype "passive"))
      (node (ref "U$14") (pin "11") (pinfunction "KL_11") (pintype "passive"))
      (node (ref "U$14") (pin "9") (pinfunction "KL_9") (pintype "passive"))
    )
    (net (code "42") (name "Net-(U$14F-KL)") (class "Default")
      (node (ref "SJ1") (pin "1") (pinfunction "1_1") (pintype "passive"))
      (node (ref "U$14") (pin "14") (pinfunction "KL_14") (pintype "passive"))
    )
    (net (code "43") (name "Net-(U$14G-KL)") (class "Default")
      (node (ref "SJ2") (pin "1") (pinfunction "1_1") (pintype "passive"))
      (node (ref "U$14") (pin "15") (pinfunction "KL_15") (pintype "passive"))
      (node (ref "U$14") (pin "16") (pinfunction "KL_16") (pintype "passive"))
    )
    (net (code "44") (name "Net-(X1C-KL)") (class "Default")
      (node (ref "R32") (pin "1") (pinfunction "1_1") (pintype "passive"))
      (node (ref "X1") (pin "11") (pinfunction "KL_11") (pintype "passive"))
      (node (ref "X1") (pin "12") (pinfunction "KL_12") (pintype "passive"))
    )
    (net (code "45") (name "Net-(X2G-KL)") (class "Default")
      (node (ref "R18") (pin "1") (pinfunction "1_1") (pintype "passive"))
      (node (ref "X2") (pin "7") (pinfunction "KL_7") (pintype "passive"))
      (node (ref "X2") (pin "8") (pinfunction "KL_8") (pintype "passive"))
    )
    (net (code "46") (name "P1.2_A2_J1.2") (class "Default")
      (node (ref "J1") (pin "2") (pinfunction "2_2") (pintype "bidirectional"))
      (node (ref "R33") (pin "2") (pinfunction "2_2") (pintype "passive"))
    )
    (net (code "47") (name "P1.3_A3_J1.6") (class "Default")
      (node (ref "J1") (pin "6") (pinfunction "6_6") (pintype "bidirectional"))
      (node (ref "R2") (pin "1") (pinfunction "1_1") (pintype "passive"))
    )
    (net (code "48") (name "P1.4_A4_J3.27") (class "Default")
      (node (ref "J3") (pin "27") (pinfunction "27_27") (pintype "bidirectional"))
      (node (ref "R7") (pin "1") (pinfunction "1_1") (pintype "passive"))
    )
    (net (code "49") (name "P1.5_A5_J3.28") (class "Default")
      (node (ref "J3") (pin "28") (pinfunction "28_28") (pintype "bidirectional"))
      (node (ref "R8") (pin "1") (pinfunction "1_1") (pintype "passive"))
    )
    (net (code "50") (name "P2.5_IO_J4.34") (class "Default")
      (node (ref "J4") (pin "34") (pinfunction "34_34") (pintype "bidirectional"))
    )
    (net (code "51") (name "P2.6_CAPTURE_J4.35") (class "Default")
      (node (ref "J4") (pin "35") (pinfunction "35_35") (pintype "bidirectional"))
    )
    (net (code "52") (name "P3.0_A12_J3.23") (class "Default")
      (node (ref "J3") (pin "23") (pinfunction "23_23") (pintype "bidirectional"))
      (node (ref "R20") (pin "2") (pinfunction "2_2") (pintype "passive"))
    )
    (net (code "53") (name "P3.1_A13_J3.24") (class "Default")
      (node (ref "C5") (pin "1") (pinfunction "1_1") (pintype "passive"))
      (node (ref "J3") (pin "24") (pinfunction "24_24") (pintype "bidirectional"))
      (node (ref "R22") (pin "2") (pinfunction "2_2") (pintype "passive"))
      (node (ref "R24") (pin "1") (pinfunction "1_1") (pintype "passive"))
    )
    (net (code "54") (name "P3.2_A14_J3.25") (class "Default")
      (node (ref "C8") (pin "1") (pinfunction "1_1") (pintype "passive"))
      (node (ref "J3") (pin "25") (pinfunction "25_25") (pintype "bidirectional"))
      (node (ref "R27") (pin "1") (pinfunction "1_1") (pintype "passive"))
      (node (ref "R28") (pin "2") (pinfunction "2_2") (pintype "passive"))
    )
    (net (code "55") (name "P3.3_A15_J3.26") (class "Default")
      (node (ref "J3") (pin "26") (pinfunction "26_26") (pintype "bidirectional"))
      (node (ref "R31") (pin "1") (pinfunction "1_1") (pintype "passive"))
      (node (ref "U$14") (pin "2") (pinfunction "KL_2") (pintype "passive"))
      (node (ref "U$16") (pin "3") (pinfunction "CATODE2_3") (pintype "passive"))
    )
    (net (code "56") (name "P3.4_PWM_J4.37") (class "Default")
      (node (ref "J4") (pin "37") (pinfunction "37_37") (pintype "bidirectional"))
      (node (ref "X1") (pin "8") (pinfunction "KL_8") (pintype "passive"))
    )
    (net (code "57") (name "P3.5_PWM_J4.38") (class "Default")
      (node (ref "J4") (pin "38") (pinfunction "38_38") (pintype "bidirectional"))
      (node (ref "X1") (pin "6") (pinfunction "KL_6") (pintype "passive"))
    )
    (net (code "58") (name "P3.6_PWM_J4.39") (class "Default")
      (node (ref "J4") (pin "39") (pinfunction "39_39") (pintype "bidirectional"))
      (node (ref "X1") (pin "4") (pinfunction "KL_4") (pintype "passive"))
    )
    (net (code "59") (name "P3.7_PWM_J4.40") (class "Default")
      (node (ref "J4") (pin "40") (pinfunction "40_40") (pintype "bidirectional"))
      (node (ref "X1") (pin "2") (pinfunction "KL_2") (pintype "passive"))
    )
    (net (code "60") (name "P4.1_IO_J4.31") (class "Default")
      (node (ref "J4") (pin "31") (pinfunction "31_31") (pintype "bidirectional"))
    )
    (net (code "61") (name "P4.2_IO_J4.32") (class "Default")
      (node (ref "J4") (pin "32") (pinfunction "32_32") (pintype "bidirectional"))
    )
    (net (code "62") (name "P4.3_IO_J4.33") (class "Default")
      (node (ref "J4") (pin "33") (pinfunction "33_33") (pintype "bidirectional"))
    )
    (net (code "63") (name "P4.4_IO_J2.18") (class "Default")
      (node (ref "J2") (pin "18") (pinfunction "18_18") (pintype "bidirectional"))
    )
    (net (code "64") (name "P4.7_IO_J3.29") (class "Default")
      (node (ref "J3") (pin "29") (pinfunction "29_29") (pintype "bidirectional"))
      (node (ref "R29") (pin "1") (pinfunction "1_1") (pintype "passive"))
    )
    (net (code "65") (name "P5.0_SPIMOSI_J2.15") (class "Default")
      (node (ref "J2") (pin "15") (pinfunction "15_15") (pintype "bidirectional"))
      (node (ref "X1") (pin "3") (pinfunction "KL_3") (pintype "passive"))
    )
    (net (code "66") (name "P5.1_SPIMISO_J2.14") (class "Default")
      (node (ref "J2") (pin "14") (pinfunction "14_14") (pintype "bidirectional"))
      (node (ref "X1") (pin "5") (pinfunction "KL_5") (pintype "passive"))
    )
    (net (code "67") (name "P5.2_SPICLK_J1.7") (class "Default")
      (node (ref "J1") (pin "7") (pinfunction "7_7") (pintype "bidirectional"))
      (node (ref "X1") (pin "7") (pinfunction "KL_7") (pintype "passive"))
    )
    (net (code "68") (name "P5.3_IO_J2.17") (class "Default")
      (node (ref "J2") (pin "17") (pinfunction "17_17") (pintype "bidirectional"))
      (node (ref "X1") (pin "1") (pinfunction "KL_1") (pintype "passive"))
    )
    (net (code "69") (name "P5.7_PWM_J2.19") (class "Default")
      (node (ref "J2") (pin "19") (pinfunction "19_19") (pintype "bidirectional"))
    )
    (net (code "70") (name "P6.0_UTXD_J1.4") (class "Default")
      (node (ref "J1") (pin "4") (pinfunction "4_4") (pintype "bidirectional"))
      (node (ref "U$14") (pin "5") (pinfunction "KL_5") (pintype "passive"))
      (node (ref "U$16") (pin "4") (pinfunction "CATODE3_4") (pintype "passive"))
      (node (ref "U$9") (pin "P$3") (pinfunction "3_P$3") (pintype "passive"))
    )
    (net (code "71") (name "P6.1_URXD_J1.3") (class "Default")
      (node (ref "J1") (pin "3") (pinfunction "3_3") (pintype "bidirectional"))
      (node (ref "U$14") (pin "3") (pinfunction "KL_3") (pintype "passive"))
      (node (ref "U$16") (pin "6") (pinfunction "CATODE5_6") (pintype "passive"))
      (node (ref "U$9") (pin "P$4") (pinfunction "4_P$4") (pintype "passive"))
    )
    (net (code "72") (name "P6.2_IO_J1.5") (class "Default")
      (node (ref "J1") (pin "5") (pinfunction "5_5") (pintype "bidirectional"))
      (node (ref "U$14") (pin "6") (pinfunction "KL_6") (pintype "passive"))
      (node (ref "U$16") (pin "5") (pinfunction "CATODE4_5") (pintype "passive"))
    )
    (net (code "73") (name "P6.3_IO_J1.8") (class "Default")
      (node (ref "J1") (pin "8") (pinfunction "8_8") (pintype "bidirectional"))
      (node (ref "U$14") (pin "4") (pinfunction "KL_4") (pintype "passive"))
      (node (ref "U$16") (pin "1") (pinfunction "CATODE1_1") (pintype "passive"))
    )
    (net (code "74") (name "P7.0_I2CSDA_J1.10") (class "Default")
      (node (ref "J1") (pin "10") (pinfunction "10_10") (pintype "bidirectional"))
      (node (ref "R13") (pin "2") (pinfunction "2_2") (pintype "passive"))
      (node (ref "U$1") (pin "5") (pinfunction "SDA_5") (pintype "bidirectional"))
      (node (ref "X2") (pin "3") (pinfunction "KL_3") (pintype "passive"))
      (node (ref "X2") (pin "4") (pinfunction "KL_4") (pintype "passive"))
    )
    (net (code "75") (name "P7.1_I2CSCL_J1.9") (class "Default")
      (node (ref "J1") (pin "9") (pinfunction "9_9") (pintype "bidirectional"))
      (node (ref "R12") (pin "2") (pinfunction "2_2") (pintype "passive"))
      (node (ref "U$1") (pin "6") (pinfunction "SCL_6") (pintype "bidirectional"))
      (node (ref "X2") (pin "1") (pinfunction "KL_1") (pintype "passive"))
      (node (ref "X2") (pin "2") (pinfunction "KL_2") (pintype "passive"))
    )
    (net (code "76") (name "P7.3_CAPTURE_J4.36") (class "Default")
      (node (ref "J4") (pin "36") (pinfunction "36_36") (pintype "bidirectional"))
    )
    (net (code "77") (name "P8.0_IO_J3.30") (class "Default")
      (node (ref "J3") (pin "30") (pinfunction "30_30") (pintype "bidirectional"))
    )
    (net (code "78") (name "P8.1_IO_J2.11") (class "Default")
      (node (ref "J2") (pin "11") (pinfunction "11_11") (pintype "bidirectional"))
      (node (ref "R36") (pin "2") (pinfunction "2_2") (pintype "passive"))
    )
    (net (code "79") (name "P8.2_IO_J2.12") (class "Default")
      (node (ref "J2") (pin "12") (pinfunction "12_12") (pintype "bidirectional"))
    )
    (net (code "80") (name "P8.3_IO_J2.13") (class "Default")
      (node (ref "J2") (pin "13") (pinfunction "13_13") (pintype "bidirectional"))
    )
    (net (code "81") (name "unconnected-(U$1-WP-Pad7)") (class "Default")
      (node (ref "U$1") (pin "7") (pinfunction "WP_7") (pintype "bidirectional"))
    )
    (net (code "82") (name "unconnected-(U$9-5-PadP$5)") (class "Default")
      (node (ref "U$9") (pin "P$5") (pinfunction "5_P$5") (pintype "passive"))
    )
    (net (code "83") (name "unconnected-(U$9-7-PadP$7)") (class "Default")
      (node (ref "U$9") (pin "P$7") (pinfunction "7_P$7") (pintype "passive"))
    )
    (net (code "84") (name "unconnected-(U$14A-KL-Pad1)") (class "Default")
      (node (ref "U$14") (pin "1") (pinfunction "KL_1") (pintype "passive"))
    )
    (net (code "85") (name "unconnected-(U$14E-KL-Pad13)") (class "Default")
      (node (ref "U$14") (pin "13") (pinfunction "KL_13") (pintype "passive"))
    )
    (net (code "86") (name "unconnected-(U$14N-KL-Pad7)") (class "Default")
      (node (ref "U$14") (pin "7") (pinfunction "KL_7") (pintype "passive"))
    )
    (net (code "87") (name "unconnected-(U$14O-KL-Pad8)") (class "Default")
      (node (ref "U$14") (pin "8") (pinfunction "KL_8") (pintype "passive"))
    )
    (net (code "88") (name "~{RST}{slash}SBWTDIO") (class "Default")
      (node (ref "J2") (pin "16") (pinfunction "16_16") (pintype "bidirectional"))
    )
  )
)
